# OmapSystem.net
KiCad netlist of a schematic drawn in Altium Designer
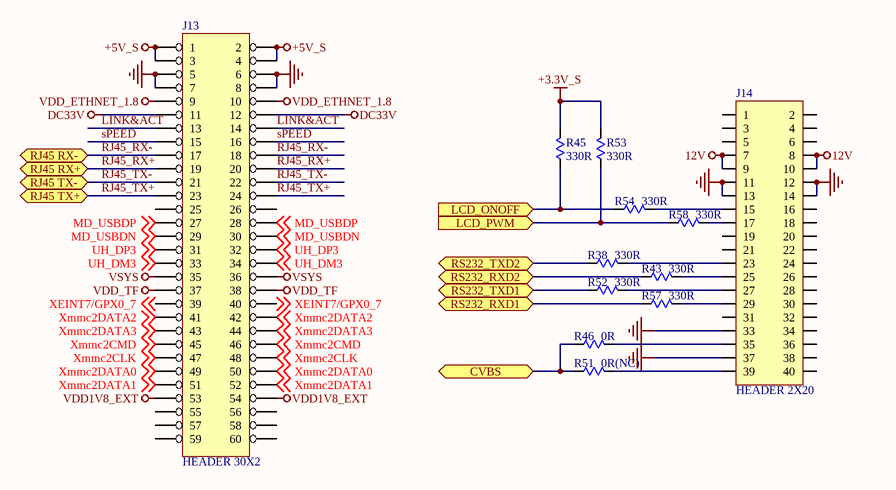
[diagram p0: OmapSystem.SchDoc]

(export (version "E")
  (design (tool "Eeschema 10.0.6"))
  (components
    (comp (ref "J13")
      (value "HEADER 30X2")
      (footprint "HD2X30-2.00")
      (libsource (lib "Connector Class") (part "HEADER 30X2"))
    )
    (comp (ref "J14")
      (value "HEADER 2X20")
      (footprint "HD2X20-2.00")
      (libsource (lib "Connector Class") (part "HEADER 2X20"))
    )
    (comp (ref "R38")
      (value "330R")
      (footprint "R1206")
      (description "Resistor")
      (fields (field (name "PUBLISHER") "Altium Limited"))
      (libsource (lib "UP-Robot") (part "Res"))
    )
    (comp (ref "R43")
      (value "330R")
      (footprint "R1206")
      (description "Resistor")
      (fields (field (name "PUBLISHER") "Altium Limited"))
      (libsource (lib "UP-Robot") (part "Res"))
    )
    (comp (ref "R45")
      (value "330R")
      (footprint "R1206")
      (description "Resistor")
      (fields (field (name "PUBLISHER") "Altium Limited"))
      (libsource (lib "UP-Robot") (part "Res"))
    )
    (comp (ref "R46")
      (value "0R")
      (footprint "R1206")
      (description "Resistor")
      (fields (field (name "PUBLISHER") "Altium Limited"))
      (libsource (lib "UP-Robot") (part "Res"))
    )
    (comp (ref "R51")
      (value "0R(NC)")
      (footprint "R1206")
      (description "Resistor")
      (fields (field (name "PUBLISHER") "Altium Limited"))
      (libsource (lib "UP-Robot") (part "Res"))
    )
    (comp (ref "R52")
      (value "330R")
      (footprint "R1206")
      (description "Resistor")
      (fields (field (name "PUBLISHER") "Altium Limited"))
      (libsource (lib "UP-Robot") (part "Res"))
    )
    (comp (ref "R53")
      (value "330R")
      (footprint "R1206")
      (description "Resistor")
      (fields (field (name "PUBLISHER") "Altium Limited"))
      (libsource (lib "UP-Robot") (part "Res"))
    )
    (comp (ref "R54")
      (value "330R")
      (footprint "R1206")
      (description "Resistor")
      (fields (field (name "PUBLISHER") "Altium Limited"))
      (libsource (lib "UP-Robot") (part "Res"))
    )
    (comp (ref "R57")
      (value "330R")
      (footprint "R1206")
      (description "Resistor")
      (fields (field (name "PUBLISHER") "Altium Limited"))
      (libsource (lib "UP-Robot") (part "Res"))
    )
    (comp (ref "R58")
      (value "330R")
      (footprint "R1206")
      (description "Resistor")
      (fields (field (name "PUBLISHER") "Altium Limited"))
      (libsource (lib "UP-Robot") (part "Res"))
    )
  )
  (nets
    (net (code "1") (name "+3.3V_S") (class "Default")
      (node (ref "R45") (pin "1") (pinfunction "1_1") (pintype "passive"))
      (node (ref "R53") (pin "1") (pinfunction "1_1") (pintype "passive"))
    )
    (net (code "2") (name "+5V_S") (class "Default")
      (node (ref "J13") (pin "1") (pinfunction "1_1") (pintype "passive"))
      (node (ref "J13") (pin "2") (pinfunction "2_2") (pintype "passive"))
      (node (ref "J13") (pin "3") (pinfunction "3_3") (pintype "passive"))
      (node (ref "J13") (pin "4") (pinfunction "4_4") (pintype "passive"))
    )
    (net (code "3") (name "/CVBS") (class "Default")
      (node (ref "R46") (pin "2") (pinfunction "2_2") (pintype "passive"))
      (node (ref "R51") (pin "2") (pinfunction "2_2") (pintype "passive"))
    )
    (net (code "4") (name "/LCD_ONOFF") (class "Default")
      (node (ref "R45") (pin "2") (pinfunction "2_2") (pintype "passive"))
      (node (ref "R54") (pin "2") (pinfunction "2_2") (pintype "passive"))
    )
    (net (code "5") (name "/LCD_PWM") (class "Default")
      (node (ref "R53") (pin "2") (pinfunction "2_2") (pintype "passive"))
      (node (ref "R58") (pin "2") (pinfunction "2_2") (pintype "passive"))
    )
    (net (code "6") (name "/LINK&ACT") (class "Default")
      (node (ref "J13") (pin "13") (pinfunction "13_13") (pintype "passive"))
      (node (ref "J13") (pin "14") (pinfunction "14_14") (pintype "passive"))
    )
    (net (code "7") (name "/RJ45_RX+") (class "Default")
      (node (ref "J13") (pin "19") (pinfunction "19_19") (pintype "passive"))
      (node (ref "J13") (pin "20") (pinfunction "20_20") (pintype "passive"))
    )
    (net (code "8") (name "/RJ45_RX-") (class "Default")
      (node (ref "J13") (pin "17") (pinfunction "17_17") (pintype "passive"))
      (node (ref "J13") (pin "18") (pinfunction "18_18") (pintype "passive"))
    )
    (net (code "9") (name "/RJ45_TX+") (class "Default")
      (node (ref "J13") (pin "23") (pinfunction "23_23") (pintype "passive"))
      (node (ref "J13") (pin "24") (pinfunction "24_24") (pintype "passive"))
    )
    (net (code "10") (name "/RJ45_TX-") (class "Default")
      (node (ref "J13") (pin "21") (pinfunction "21_21") (pintype "passive"))
      (node (ref "J13") (pin "22") (pinfunction "22_22") (pintype "passive"))
    )
    (net (code "11") (name "/RS232_RXD1") (class "Default")
      (node (ref "R57") (pin "2") (pinfunction "2_2") (pintype "passive"))
    )
    (net (code "12") (name "/RS232_RXD2") (class "Default")
      (node (ref "R43") (pin "2") (pinfunction "2_2") (pintype "passive"))
    )
    (net (code "13") (name "/RS232_TXD1") (class "Default")
      (node (ref "R52") (pin "2") (pinfunction "2_2") (pintype "passive"))
    )
    (net (code "14") (name "/RS232_TXD2") (class "Default")
      (node (ref "R38") (pin "2") (pinfunction "2_2") (pintype "passive"))
    )
    (net (code "15") (name "/sPEED") (class "Default")
      (node (ref "J13") (pin "15") (pinfunction "15_15") (pintype "passive"))
      (node (ref "J13") (pin "16") (pinfunction "16_16") (pintype "passive"))
    )
    (net (code "16") (name "12V") (class "Default")
      (node (ref "J14") (pin "10") (pinfunction "10_10") (pintype "passive"))
      (node (ref "J14") (pin "7") (pinfunction "7_7") (pintype "passive"))
      (node (ref "J14") (pin "8") (pinfunction "8_8") (pintype "passive"))
      (node (ref "J14") (pin "9") (pinfunction "9_9") (pintype "passive"))
    )
    (net (code "17") (name "DC33V") (class "Default")
      (node (ref "J13") (pin "11") (pinfunction "11_11") (pintype "passive"))
      (node (ref "J13") (pin "12") (pinfunction "12_12") (pintype "passive"))
    )
    (net (code "18") (name "MD_USBDN") (class "Default")
      (node (ref "J13") (pin "29") (pinfunction "29_29") (pintype "passive"))
      (node (ref "J13") (pin "30") (pinfunction "30_30") (pintype "passive"))
    )
    (net (code "19") (name "MD_USBDP") (class "Default")
      (node (ref "J13") (pin "27") (pinfunction "27_27") (pintype "passive"))
      (node (ref "J13") (pin "28") (pinfunction "28_28") (pintype "passive"))
    )
    (net (code "20") (name "Net-(J14-Pad15)") (class "Default")
      (node (ref "J14") (pin "15") (pinfunction "15_15") (pintype "passive"))
      (node (ref "R54") (pin "1") (pinfunction "1_1") (pintype "passive"))
    )
    (net (code "21") (name "Net-(J14-Pad17)") (class "Default")
      (node (ref "J14") (pin "17") (pinfunction "17_17") (pintype "passive"))
      (node (ref "R58") (pin "1") (pinfunction "1_1") (pintype "passive"))
    )
    (net (code "22") (name "Net-(J14-Pad23)") (class "Default")
      (node (ref "J14") (pin "23") (pinfunction "23_23") (pintype "passive"))
      (node (ref "R38") (pin "1") (pinfunction "1_1") (pintype "passive"))
    )
    (net (code "23") (name "Net-(J14-Pad25)") (class "Default")
      (node (ref "J14") (pin "25") (pinfunction "25_25") (pintype "passive"))
      (node (ref "R43") (pin "1") (pinfunction "1_1") (pintype "passive"))
    )
    (net (code "24") (name "Net-(J14-Pad27)") (class "Default")
      (node (ref "J14") (pin "27") (pinfunction "27_27") (pintype "passive"))
      (node (ref "R52") (pin "1") (pinfunction "1_1") (pintype "passive"))
    )
    (net (code "25") (name "Net-(J14-Pad29)") (class "Default")
      (node (ref "J14") (pin "29") (pinfunction "29_29") (pintype "passive"))
      (node (ref "R57") (pin "1") (pinfunction "1_1") (pintype "passive"))
    )
    (net (code "26") (name "Net-(J14-Pad35)") (class "Default")
      (node (ref "J14") (pin "35") (pinfunction "35_35") (pintype "passive"))
      (node (ref "R46") (pin "1") (pinfunction "1_1") (pintype "passive"))
    )
    (net (code "27") (name "Net-(J14-Pad39)") (class "Default")
      (node (ref "J14") (pin "39") (pinfunction "39_39") (pintype "passive"))
      (node (ref "R51") (pin "1") (pinfunction "1_1") (pintype "passive"))
    )
    (net (code "28") (name "SGND") (class "Default")
      (node (ref "J13") (pin "5") (pinfunction "5_5") (pintype "passive"))
      (node (ref "J13") (pin "6") (pinfunction "6_6") (pintype "passive"))
      (node (ref "J13") (pin "7") (pinfunction "7_7") (pintype "passive"))
      (node (ref "J13") (pin "8") (pinfunction "8_8") (pintype "passive"))
      (node (ref "J14") (pin "11") (pinfunction "11_11") (pintype "passive"))
      (node (ref "J14") (pin "12") (pinfunction "12_12") (pintype "passive"))
      (node (ref "J14") (pin "13") (pinfunction "13_13") (pintype "passive"))
      (node (ref "J14") (pin "14") (pinfunction "14_14") (pintype "passive"))
      (node (ref "J14") (pin "33") (pinfunction "33_33") (pintype "passive"))
      (node (ref "J14") (pin "37") (pinfunction "37_37") (pintype "passive"))
    )
    (net (code "29") (name "UH_DM3") (class "Default")
      (node (ref "J13") (pin "33") (pinfunction "33_33") (pintype "passive"))
      (node (ref "J13") (pin "34") (pinfunction "34_34") (pintype "passive"))
    )
    (net (code "30") (name "UH_DP3") (class "Default")
      (node (ref "J13") (pin "31") (pinfunction "31_31") (pintype "passive"))
      (node (ref "J13") (pin "32") (pinfunction "32_32") (pintype "passive"))
    )
    (net (code "31") (name "VDD1V8_EXT") (class "Default")
      (node (ref "J13") (pin "53") (pinfunction "53_53") (pintype "passive"))
      (node (ref "J13") (pin "54") (pinfunction "54_54") (pintype "passive"))
    )
    (net (code "32") (name "VDD_ETHNET_1.8") (class "Default")
      (node (ref "J13") (pin "10") (pinfunction "10_10") (pintype "passive"))
      (node (ref "J13") (pin "9") (pinfunction "9_9") (pintype "passive"))
    )
    (net (code "33") (name "VDD_TF") (class "Default")
      (node (ref "J13") (pin "37") (pinfunction "37_37") (pintype "passive"))
      (node (ref "J13") (pin "38") (pinfunction "38_38") (pintype "passive"))
    )
    (net (code "34") (name "VSYS") (class "Default")
      (node (ref "J13") (pin "35") (pinfunction "35_35") (pintype "passive"))
      (node (ref "J13") (pin "36") (pinfunction "36_36") (pintype "passive"))
    )
    (net (code "35") (name "XEINT7{slash}GPX0_7") (class "Default")
      (node (ref "J13") (pin "39") (pinfunction "39_39") (pintype "passive"))
      (node (ref "J13") (pin "40") (pinfunction "40_40") (pintype "passive"))
    )
    (net (code "36") (name "Xmmc2CLK") (class "Default")
      (node (ref "J13") (pin "47") (pinfunction "47_47") (pintype "passive"))
      (node (ref "J13") (pin "48") (pinfunction "48_48") (pintype "passive"))
    )
    (net (code "37") (name "Xmmc2CMD") (class "Default")
      (node (ref "J13") (pin "45") (pinfunction "45_45") (pintype "passive"))
      (node (ref "J13") (pin "46") (pinfunction "46_46") (pintype "passive"))
    )
    (net (code "38") (name "Xmmc2DATA0") (class "Default")
      (node (ref "J13") (pin "49") (pinfunction "49_49") (pintype "passive"))
      (node (ref "J13") (pin "50") (pinfunction "50_50") (pintype "passive"))
    )
    (net (code "39") (name "Xmmc2DATA1") (class "Default")
      (node (ref "J13") (pin "51") (pinfunction "51_51") (pintype "passive"))
      (node (ref "J13") (pin "52") (pinfunction "52_52") (pintype "passive"))
    )
    (net (code "40") (name "Xmmc2DATA2") (class "Default")
      (node (ref "J13") (pin "41") (pinfunction "41_41") (pintype "passive"))
      (node (ref "J13") (pin "42") (pinfunction "42_42") (pintype "passive"))
    )
    (net (code "41") (name "Xmmc2DATA3") (class "Default")
      (node (ref "J13") (pin "43") (pinfunction "43_43") (pintype "passive"))
      (node (ref "J13") (pin "44") (pinfunction "44_44") (pintype "passive"))
    )
    (net (code "42") (name "unconnected-(J13-Pad25)") (class "Default")
      (node (ref "J13") (pin "25") (pinfunction "25_25") (pintype "passive"))
    )
    (net (code "43") (name "unconnected-(J13-Pad26)") (class "Default")
      (node (ref "J13") (pin "26") (pinfunction "26_26") (pintype "passive"))
    )
    (net (code "44") (name "unconnected-(J13-Pad55)") (class "Default")
      (node (ref "J13") (pin "55") (pinfunction "55_55") (pintype "passive"))
    )
    (net (code "45") (name "unconnected-(J13-Pad56)") (class "Default")
      (node (ref "J13") (pin "56") (pinfunction "56_56") (pintype "passive"))
    )
    (net (code "46") (name "unconnected-(J13-Pad57)") (class "Default")
      (node (ref "J13") (pin "57") (pinfunction "57_57") (pintype "passive"))
    )
    (net (code "47") (name "unconnected-(J13-Pad58)") (class "Default")
      (node (ref "J13") (pin "58") (pinfunction "58_58") (pintype "passive"))
    )
    (net (code "48") (name "unconnected-(J13-Pad59)") (class "Default")
      (node (ref "J13") (pin "59") (pinfunction "59_59") (pintype "passive"))
    )
    (net (code "49") (name "unconnected-(J13-Pad60)") (class "Default")
      (node (ref "J13") (pin "60") (pinfunction "60_60") (pintype "passive"))
    )
    (net (code "50") (name "unconnected-(J14-Pad1)") (class "Default")
      (node (ref "J14") (pin "1") (pinfunction "1_1") (pintype "passive"))
    )
    (net (code "51") (name "unconnected-(J14-Pad2)") (class "Default")
      (node (ref "J14") (pin "2") (pinfunction "2_2") (pintype "passive"))
    )
    (net (code "52") (name "unconnected-(J14-Pad3)") (class "Default")
      (node (ref "J14") (pin "3") (pinfunction "3_3") (pintype "passive"))
    )
    (net (code "53") (name "unconnected-(J14-Pad4)") (class "Default")
      (node (ref "J14") (pin "4") (pinfunction "4_4") (pintype "passive"))
    )
    (net (code "54") (name "unconnected-(J14-Pad5)") (class "Default")
      (node (ref "J14") (pin "5") (pinfunction "5_5") (pintype "passive"))
    )
    (net (code "55") (name "unconnected-(J14-Pad6)") (class "Default")
      (node (ref "J14") (pin "6") (pinfunction "6_6") (pintype "passive"))
    )
    (net (code "56") (name "unconnected-(J14-Pad16)") (class "Default")
      (node (ref "J14") (pin "16") (pinfunction "16_16") (pintype "passive"))
    )
    (net (code "57") (name "unconnected-(J14-Pad18)") (class "Default")
      (node (ref "J14") (pin "18") (pinfunction "18_18") (pintype "passive"))
    )
    (net (code "58") (name "unconnected-(J14-Pad19)") (class "Default")
      (node (ref "J14") (pin "19") (pinfunction "19_19") (pintype "passive"))
    )
    (net (code "59") (name "unconnected-(J14-Pad20)") (class "Default")
      (node (ref "J14") (pin "20") (pinfunction "20_20") (pintype "passive"))
    )
    (net (code "60") (name "unconnected-(J14-Pad21)") (class "Default")
      (node (ref "J14") (pin "21") (pinfunction "21_21") (pintype "passive"))
    )
    (net (code "61") (name "unconnected-(J14-Pad22)") (class "Default")
      (node (ref "J14") (pin "22") (pinfunction "22_22") (pintype "passive"))
    )
    (net (code "62") (name "unconnected-(J14-Pad24)") (class "Default")
      (node (ref "J14") (pin "24") (pinfunction "24_24") (pintype "passive"))
    )
    (net (code "63") (name "unconnected-(J14-Pad26)") (class "Default")
      (node (ref "J14") (pin "26") (pinfunction "26_26") (pintype "passive"))
    )
    (net (code "64") (name "unconnected-(J14-Pad28)") (class "Default")
      (node (ref "J14") (pin "28") (pinfunction "28_28") (pintype "passive"))
    )
    (net (code "65") (name "unconnected-(J14-Pad30)") (class "Default")
      (node (ref "J14") (pin "30") (pinfunction "30_30") (pintype "passive"))
    )
    (net (code "66") (name "unconnected-(J14-Pad31)") (class "Default")
      (node (ref "J14") (pin "31") (pinfunction "31_31") (pintype "passive"))
    )
    (net (code "67") (name "unconnected-(J14-Pad32)") (class "Default")
      (node (ref "J14") (pin "32") (pinfunction "32_32") (pintype "passive"))
    )
    (net (code "68") (name "unconnected-(J14-Pad34)") (class "Default")
      (node (ref "J14") (pin "34") (pinfunction "34_34") (pintype "passive"))
    )
    (net (code "69") (name "unconnected-(J14-Pad36)") (class "Default")
      (node (ref "J14") (pin "36") (pinfunction "36_36") (pintype "passive"))
    )
    (net (code "70") (name "unconnected-(J14-Pad38)") (class "Default")
      (node (ref "J14") (pin "38") (pinfunction "38_38") (pintype "passive"))
    )
    (net (code "71") (name "unconnected-(J14-Pad40)") (class "Default")
      (node (ref "J14") (pin "40") (pinfunction "40_40") (pintype "passive"))
    )
  )
)
